# stm32rf_node.net
KiCad netlist of a schematic drawn in EAGLE
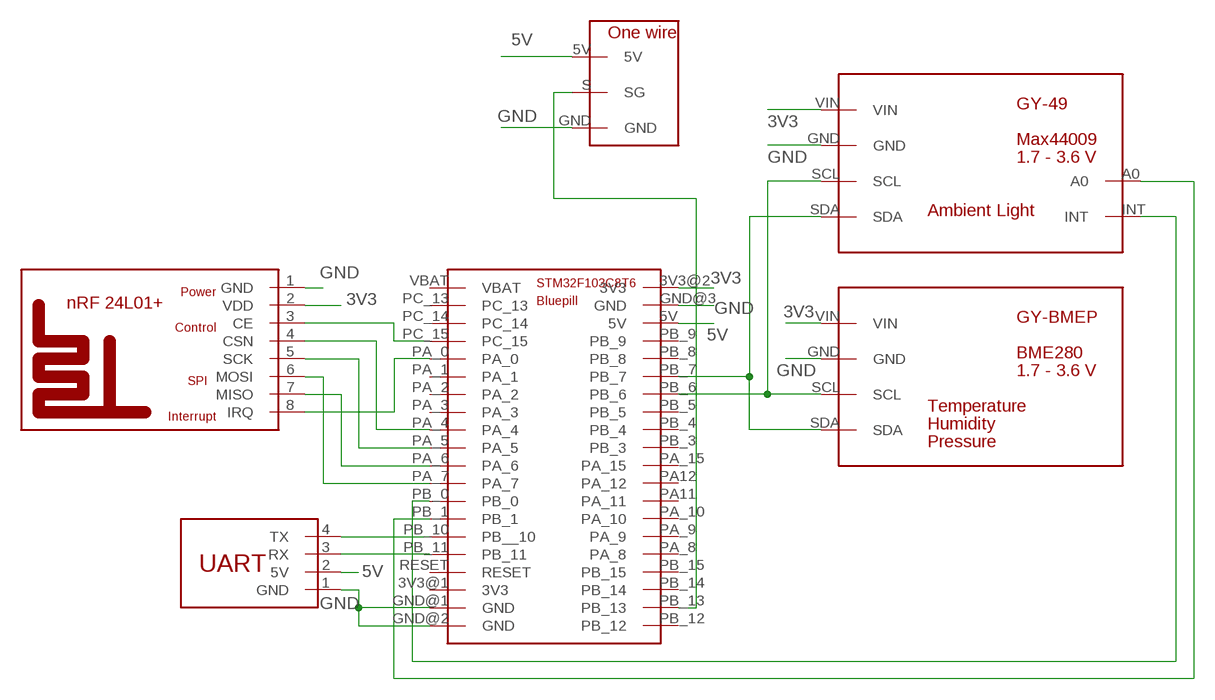
[diagram p0: schematic, sheet 1]

(export (version "E")
  (design (tool "Eeschema 10.0.6"))
  (components
    (comp (ref "U$1")
      (value "STM32_BLUEPILL")
      (footprint "eagle-import:STM32_BLUEPILL")
      (libsource (lib "eagle-import") (part "STM32_BLUEPILL"))
    )
    (comp (ref "U$2")
      (value "NRF24L01+REFDESIGNMINI")
      (footprint "eagle-import:NRF24L01+REFDESIGN-MINI")
      (libsource (lib "eagle-import") (part "NRF24L01+REFDESIGNMINI"))
    )
    (comp (ref "U$3")
      (value "GY-BMEPGY-BMEP-NOHOLE")
      (footprint "eagle-import:GY-BMEP-NOHOLE")
      (libsource (lib "eagle-import") (part "GY-BMEPGY-BMEP-NOHOLE"))
    )
    (comp (ref "U$4")
      (value "GY-49G-49-SURF")
      (footprint "eagle-import:GY-49-SURF")
      (libsource (lib "eagle-import") (part "GY-49G-49-SURF"))
    )
    (comp (ref "U$5")
      (value "ONE_WIRE'RIGHT'")
      (footprint "eagle-import:ONE_WIRE_RIGHT")
      (libsource (lib "eagle-import") (part "ONE_WIRE'RIGHT'"))
    )
    (comp (ref "U$6")
      (value "UARTMINI")
      (footprint "eagle-import:UART-MINI")
      (libsource (lib "eagle-import") (part "UARTMINI"))
    )
  )
  (nets
    (net (code "1") (name "/3V3") (class "Default")
      (node (ref "U$1") (pin "3V3@2") (pinfunction "3V3_3V3@2") (pintype "bidirectional"))
      (node (ref "U$2") (pin "2") (pinfunction "VDD_2") (pintype "bidirectional"))
      (node (ref "U$3") (pin "VIN") (pinfunction "VIN_VIN") (pintype "bidirectional"))
      (node (ref "U$4") (pin "VIN") (pinfunction "VIN_VIN") (pintype "bidirectional"))
    )
    (net (code "2") (name "/5V") (class "Default")
      (node (ref "U$1") (pin "5V") (pinfunction "5V_5V") (pintype "bidirectional"))
      (node (ref "U$5") (pin "5V") (pinfunction "5V_5V") (pintype "bidirectional"))
      (node (ref "U$6") (pin "2") (pinfunction "5V_2") (pintype "bidirectional"))
    )
    (net (code "3") (name "/GND") (class "Default")
      (node (ref "U$1") (pin "GND@1") (pinfunction "GND_GND@1") (pintype "bidirectional"))
      (node (ref "U$1") (pin "GND@2") (pinfunction "GND_GND@2") (pintype "bidirectional"))
      (node (ref "U$1") (pin "GND@3") (pinfunction "GND_GND@3") (pintype "bidirectional"))
      (node (ref "U$2") (pin "1") (pinfunction "GND_1") (pintype "bidirectional"))
      (node (ref "U$3") (pin "GND") (pinfunction "GND_GND") (pintype "bidirectional"))
      (node (ref "U$4") (pin "GND") (pinfunction "GND_GND") (pintype "bidirectional"))
      (node (ref "U$5") (pin "GND") (pinfunction "GND_GND") (pintype "bidirectional"))
      (node (ref "U$6") (pin "1") (pinfunction "GND_1") (pintype "bidirectional"))
    )
    (net (code "4") (name "Net-(U$1-PB__10)") (class "Default")
      (node (ref "U$1") (pin "PB_10") (pinfunction "PB__10_PB_10") (pintype "bidirectional"))
      (node (ref "U$6") (pin "4") (pinfunction "TX_4") (pintype "bidirectional"))
    )
    (net (code "5") (name "Net-(U$1-PadPB_0)") (class "Default")
      (node (ref "U$1") (pin "PB_0") (pinfunction "PB_0_PB_0") (pintype "bidirectional"))
      (node (ref "U$4") (pin "INT") (pinfunction "INT_INT") (pintype "bidirectional"))
    )
    (net (code "6") (name "Net-(U$1-PadPB_1)") (class "Default")
      (node (ref "U$1") (pin "PB_1") (pinfunction "PB_1_PB_1") (pintype "bidirectional"))
      (node (ref "U$4") (pin "A0") (pinfunction "A0_A0") (pintype "bidirectional"))
    )
    (net (code "7") (name "Net-(U$1-PadPB_6)") (class "Default")
      (node (ref "U$1") (pin "PB_6") (pinfunction "PB_6_PB_6") (pintype "bidirectional"))
      (node (ref "U$3") (pin "SCL") (pinfunction "SCL_SCL") (pintype "bidirectional"))
      (node (ref "U$4") (pin "SCL") (pinfunction "SCL_SCL") (pintype "bidirectional"))
    )
    (net (code "8") (name "Net-(U$1-PadPB_7)") (class "Default")
      (node (ref "U$1") (pin "PB_7") (pinfunction "PB_7_PB_7") (pintype "bidirectional"))
      (node (ref "U$3") (pin "SDA") (pinfunction "SDA_SDA") (pintype "bidirectional"))
      (node (ref "U$4") (pin "SDA") (pinfunction "SDA_SDA") (pintype "bidirectional"))
    )
    (net (code "9") (name "Net-(U$2-CE)") (class "Default")
      (node (ref "U$1") (pin "PC_15") (pinfunction "PC_15_PC_15") (pintype "bidirectional"))
      (node (ref "U$2") (pin "3") (pinfunction "CE_3") (pintype "bidirectional"))
    )
    (net (code "10") (name "Net-(U$2-CSN)") (class "Default")
      (node (ref "U$1") (pin "PA_4") (pinfunction "PA_4_PA_4") (pintype "bidirectional"))
      (node (ref "U$2") (pin "4") (pinfunction "CSN_4") (pintype "bidirectional"))
    )
    (net (code "11") (name "Net-(U$2-IRQ)") (class "Default")
      (node (ref "U$1") (pin "PA_0") (pinfunction "PA_0_PA_0") (pintype "bidirectional"))
      (node (ref "U$2") (pin "8") (pinfunction "IRQ_8") (pintype "bidirectional"))
    )
    (net (code "12") (name "Net-(U$2-MISO)") (class "Default")
      (node (ref "U$1") (pin "PA_6") (pinfunction "PA_6_PA_6") (pintype "bidirectional"))
      (node (ref "U$2") (pin "7") (pinfunction "MISO_7") (pintype "bidirectional"))
    )
    (net (code "13") (name "Net-(U$2-MOSI)") (class "Default")
      (node (ref "U$1") (pin "PA_7") (pinfunction "PA_7_PA_7") (pintype "bidirectional"))
      (node (ref "U$2") (pin "6") (pinfunction "MOSI_6") (pintype "bidirectional"))
    )
    (net (code "14") (name "Net-(U$2-SCK)") (class "Default")
      (node (ref "U$1") (pin "PA_5") (pinfunction "PA_5_PA_5") (pintype "bidirectional"))
      (node (ref "U$2") (pin "5") (pinfunction "SCK_5") (pintype "bidirectional"))
    )
    (net (code "15") (name "Net-(U$5-SG)") (class "Default")
      (node (ref "U$1") (pin "PB_13") (pinfunction "PB_13_PB_13") (pintype "bidirectional"))
      (node (ref "U$5") (pin "S") (pinfunction "SG_S") (pintype "bidirectional"))
    )
    (net (code "16") (name "Net-(U$6-RX)") (class "Default")
      (node (ref "U$1") (pin "PB_11") (pinfunction "PB_11_PB_11") (pintype "bidirectional"))
      (node (ref "U$6") (pin "3") (pinfunction "RX_3") (pintype "bidirectional"))
    )
    (net (code "17") (name "unconnected-(U$1-3V3-Pad3V3@1)") (class "Default")
      (node (ref "U$1") (pin "3V3@1") (pinfunction "3V3_3V3@1") (pintype "bidirectional"))
    )
    (net (code "18") (name "unconnected-(U$1-PA_11-PadPA11)") (class "Default")
      (node (ref "U$1") (pin "PA11") (pinfunction "PA_11_PA11") (pintype "bidirectional"))
    )
    (net (code "19") (name "unconnected-(U$1-PA_12-PadPA12)") (class "Default")
      (node (ref "U$1") (pin "PA12") (pinfunction "PA_12_PA12") (pintype "bidirectional"))
    )
    (net (code "20") (name "unconnected-(U$1-PadPA_1)") (class "Default")
      (node (ref "U$1") (pin "PA_1") (pinfunction "PA_1_PA_1") (pintype "bidirectional"))
    )
    (net (code "21") (name "unconnected-(U$1-PadPA_2)") (class "Default")
      (node (ref "U$1") (pin "PA_2") (pinfunction "PA_2_PA_2") (pintype "bidirectional"))
    )
    (net (code "22") (name "unconnected-(U$1-PadPA_3)") (class "Default")
      (node (ref "U$1") (pin "PA_3") (pinfunction "PA_3_PA_3") (pintype "bidirectional"))
    )
    (net (code "23") (name "unconnected-(U$1-PadPA_8)") (class "Default")
      (node (ref "U$1") (pin "PA_8") (pinfunction "PA_8_PA_8") (pintype "bidirectional"))
    )
    (net (code "24") (name "unconnected-(U$1-PadPA_9)") (class "Default")
      (node (ref "U$1") (pin "PA_9") (pinfunction "PA_9_PA_9") (pintype "bidirectional"))
    )
    (net (code "25") (name "unconnected-(U$1-PadPA_10)") (class "Default")
      (node (ref "U$1") (pin "PA_10") (pinfunction "PA_10_PA_10") (pintype "bidirectional"))
    )
    (net (code "26") (name "unconnected-(U$1-PadPA_15)") (class "Default")
      (node (ref "U$1") (pin "PA_15") (pinfunction "PA_15_PA_15") (pintype "bidirectional"))
    )
    (net (code "27") (name "unconnected-(U$1-PadPB_3)") (class "Default")
      (node (ref "U$1") (pin "PB_3") (pinfunction "PB_3_PB_3") (pintype "bidirectional"))
    )
    (net (code "28") (name "unconnected-(U$1-PadPB_4)") (class "Default")
      (node (ref "U$1") (pin "PB_4") (pinfunction "PB_4_PB_4") (pintype "bidirectional"))
    )
    (net (code "29") (name "unconnected-(U$1-PadPB_5)") (class "Default")
      (node (ref "U$1") (pin "PB_5") (pinfunction "PB_5_PB_5") (pintype "bidirectional"))
    )
    (net (code "30") (name "unconnected-(U$1-PadPB_8)") (class "Default")
      (node (ref "U$1") (pin "PB_8") (pinfunction "PB_8_PB_8") (pintype "bidirectional"))
    )
    (net (code "31") (name "unconnected-(U$1-PadPB_9)") (class "Default")
      (node (ref "U$1") (pin "PB_9") (pinfunction "PB_9_PB_9") (pintype "bidirectional"))
    )
    (net (code "32") (name "unconnected-(U$1-PadPB_12)") (class "Default")
      (node (ref "U$1") (pin "PB_12") (pinfunction "PB_12_PB_12") (pintype "bidirectional"))
    )
    (net (code "33") (name "unconnected-(U$1-PadPB_14)") (class "Default")
      (node (ref "U$1") (pin "PB_14") (pinfunction "PB_14_PB_14") (pintype "bidirectional"))
    )
    (net (code "34") (name "unconnected-(U$1-PadPB_15)") (class "Default")
      (node (ref "U$1") (pin "PB_15") (pinfunction "PB_15_PB_15") (pintype "bidirectional"))
    )
    (net (code "35") (name "unconnected-(U$1-PadPC_13)") (class "Default")
      (node (ref "U$1") (pin "PC_13") (pinfunction "PC_13_PC_13") (pintype "bidirectional"))
    )
    (net (code "36") (name "unconnected-(U$1-PadPC_14)") (class "Default")
      (node (ref "U$1") (pin "PC_14") (pinfunction "PC_14_PC_14") (pintype "bidirectional"))
    )
    (net (code "37") (name "unconnected-(U$1-PadRESET)") (class "Default")
      (node (ref "U$1") (pin "RESET") (pinfunction "RESET_RESET") (pintype "bidirectional"))
    )
    (net (code "38") (name "unconnected-(U$1-PadVBAT)") (class "Default")
      (node (ref "U$1") (pin "VBAT") (pinfunction "VBAT_VBAT") (pintype "bidirectional"))
    )
  )
)
